# ITF_switching.net
KiCad netlist of a schematic drawn in EAGLE
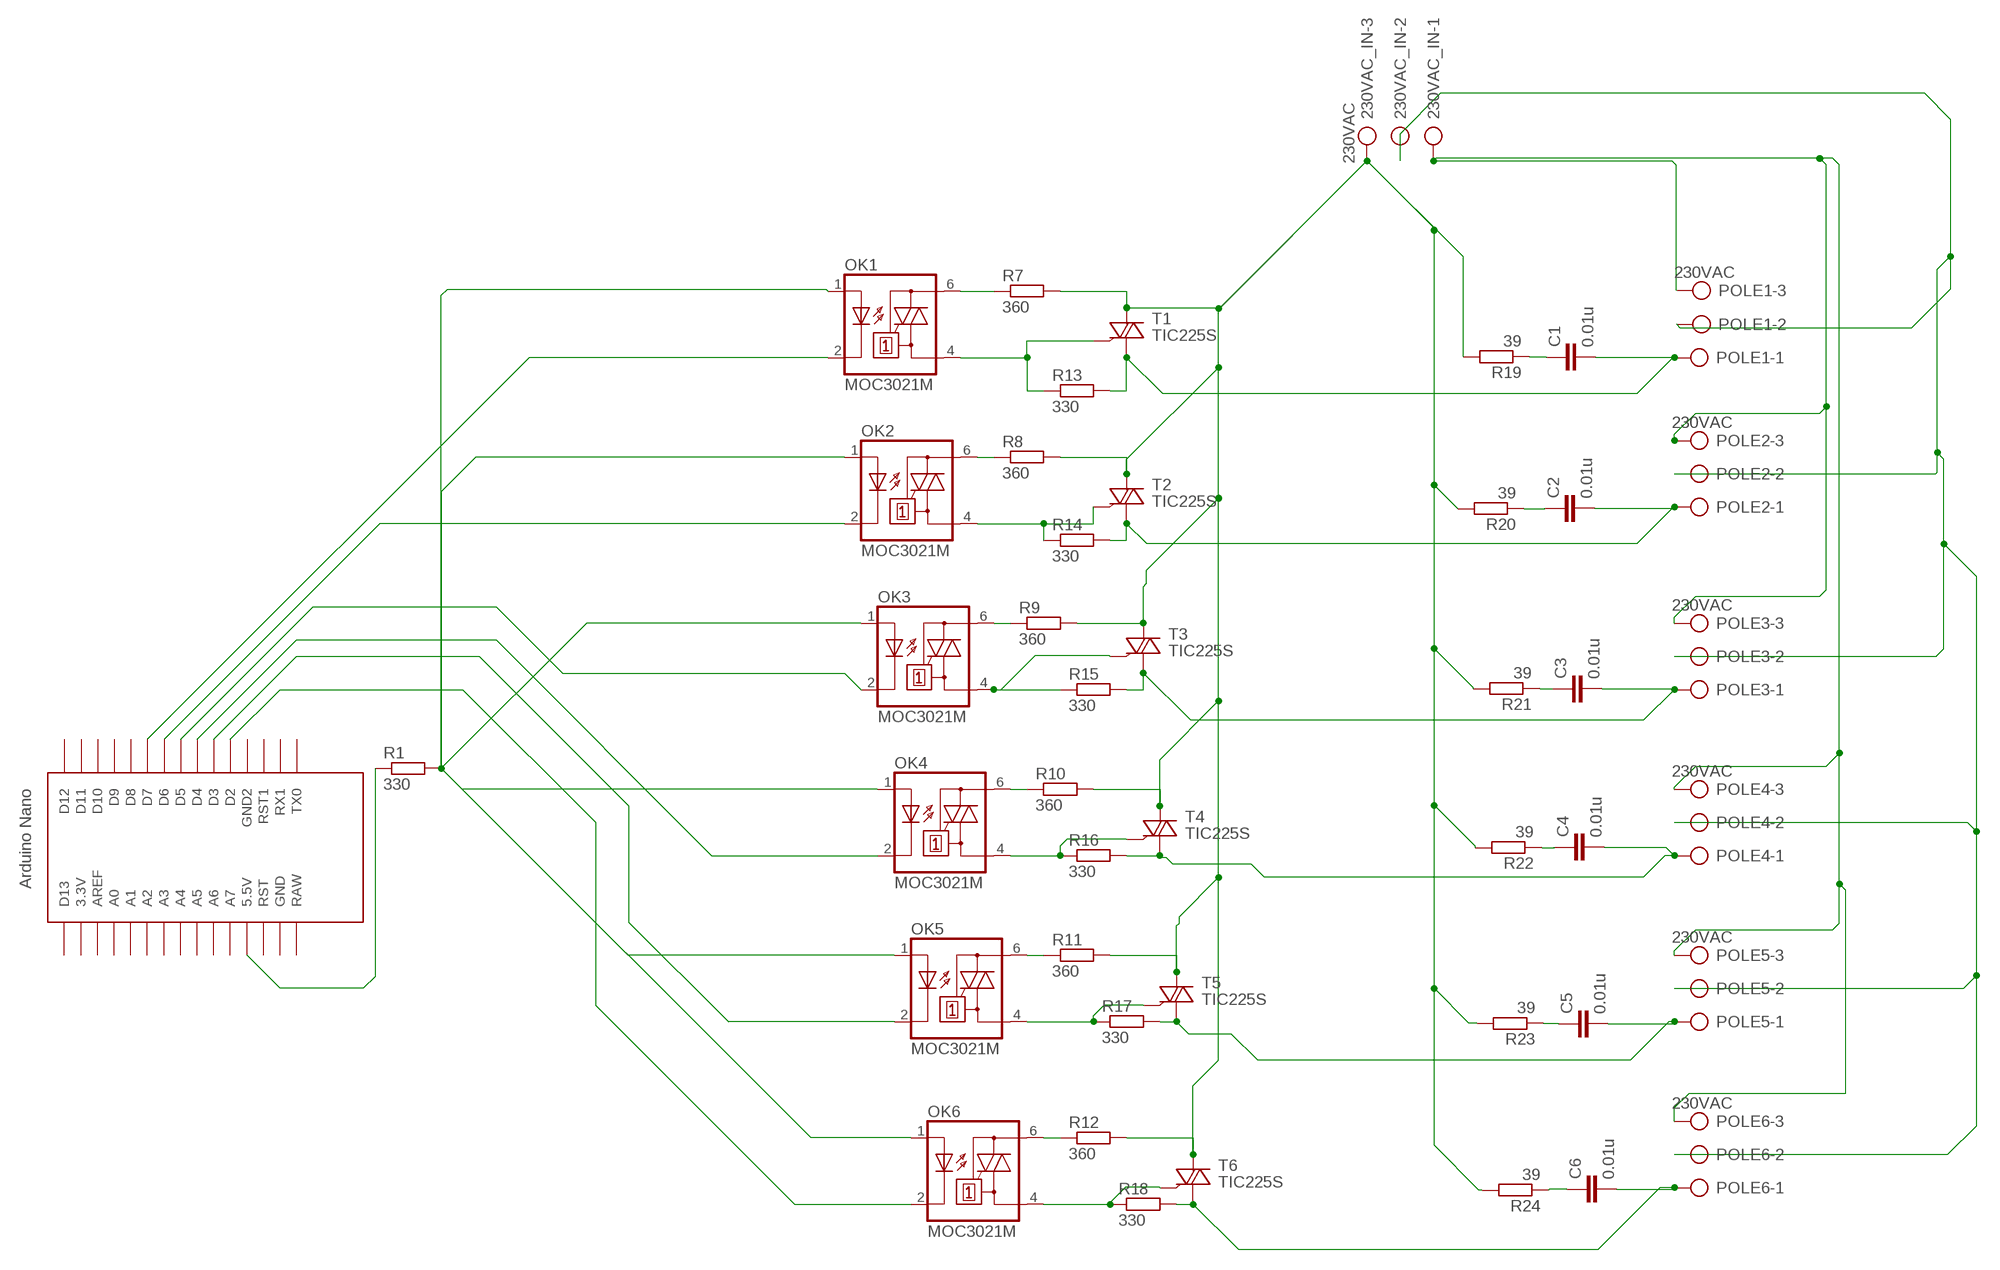
[diagram p0: schematic, sheet 1]

(export (version "E")
  (design (tool "Eeschema 10.0.6"))
  (components
    (comp (ref "230VAC_IN")
      (value "230VAC")
      (footprint "eagle-import:AK300_3")
      (libsource (lib "eagle-import") (part "AK300/3"))
    )
    (comp (ref "C1")
      (value "0.01u")
      (footprint "eagle-import:C2.5-6")
      (libsource (lib "eagle-import") (part "C2.5/6"))
    )
    (comp (ref "C2")
      (value "0.01u")
      (footprint "eagle-import:C2.5-6")
      (libsource (lib "eagle-import") (part "C2.5/6"))
    )
    (comp (ref "C3")
      (value "0.01u")
      (footprint "eagle-import:C2.5-6")
      (libsource (lib "eagle-import") (part "C2.5/6"))
    )
    (comp (ref "C4")
      (value "0.01u")
      (footprint "eagle-import:C2.5-6")
      (libsource (lib "eagle-import") (part "C2.5/6"))
    )
    (comp (ref "C5")
      (value "0.01u")
      (footprint "eagle-import:C2.5-6")
      (libsource (lib "eagle-import") (part "C2.5/6"))
    )
    (comp (ref "C6")
      (value "0.01u")
      (footprint "eagle-import:C2.5-6")
      (libsource (lib "eagle-import") (part "C2.5/6"))
    )
    (comp (ref "OK1")
      (value "MOC3021M")
      (footprint "eagle-import:DIL06")
      (fields (field (name "MF") "FAIRCHILD SEMICONDUCTOR") (field (name "MPN") "MOC3021-M"))
      (libsource (lib "eagle-import") (part "MOC30M21"))
    )
    (comp (ref "OK2")
      (value "MOC3021M")
      (footprint "eagle-import:DIL06")
      (fields (field (name "MF") "FAIRCHILD SEMICONDUCTOR") (field (name "MPN") "MOC3021-M"))
      (libsource (lib "eagle-import") (part "MOC30M21"))
    )
    (comp (ref "OK3")
      (value "MOC3021M")
      (footprint "eagle-import:DIL06")
      (fields (field (name "MF") "FAIRCHILD SEMICONDUCTOR") (field (name "MPN") "MOC3021-M"))
      (libsource (lib "eagle-import") (part "MOC30M21"))
    )
    (comp (ref "OK4")
      (value "MOC3021M")
      (footprint "eagle-import:DIL06")
      (fields (field (name "MF") "FAIRCHILD SEMICONDUCTOR") (field (name "MPN") "MOC3021-M"))
      (libsource (lib "eagle-import") (part "MOC30M21"))
    )
    (comp (ref "OK5")
      (value "MOC3021M")
      (footprint "eagle-import:DIL06")
      (fields (field (name "MF") "FAIRCHILD SEMICONDUCTOR") (field (name "MPN") "MOC3021-M"))
      (libsource (lib "eagle-import") (part "MOC30M21"))
    )
    (comp (ref "OK6")
      (value "MOC3021M")
      (footprint "eagle-import:DIL06")
      (fields (field (name "MF") "FAIRCHILD SEMICONDUCTOR") (field (name "MPN") "MOC3021-M"))
      (libsource (lib "eagle-import") (part "MOC30M21"))
    )
    (comp (ref "POLE1")
      (value "230VAC")
      (footprint "eagle-import:AK300_3")
      (libsource (lib "eagle-import") (part "AK300/3"))
    )
    (comp (ref "POLE2")
      (value "230VAC")
      (footprint "eagle-import:AK300_3")
      (libsource (lib "eagle-import") (part "AK300/3"))
    )
    (comp (ref "POLE3")
      (value "230VAC")
      (footprint "eagle-import:AK300_3")
      (libsource (lib "eagle-import") (part "AK300/3"))
    )
    (comp (ref "POLE4")
      (value "230VAC")
      (footprint "eagle-import:AK300_3")
      (libsource (lib "eagle-import") (part "AK300/3"))
    )
    (comp (ref "POLE5")
      (value "230VAC")
      (footprint "eagle-import:AK300_3")
      (libsource (lib "eagle-import") (part "AK300/3"))
    )
    (comp (ref "POLE6")
      (value "230VAC")
      (footprint "eagle-import:AK300_3")
      (libsource (lib "eagle-import") (part "AK300/3"))
    )
    (comp (ref "R1")
      (value "330")
      (footprint "eagle-import:0207_10")
      (libsource (lib "eagle-import") (part "R-EU_0207/10"))
    )
    (comp (ref "R7")
      (value "360")
      (footprint "eagle-import:0207_10")
      (libsource (lib "eagle-import") (part "R-EU_0207/10"))
    )
    (comp (ref "R8")
      (value "360")
      (footprint "eagle-import:0207_10")
      (libsource (lib "eagle-import") (part "R-EU_0207/10"))
    )
    (comp (ref "R9")
      (value "360")
      (footprint "eagle-import:0207_10")
      (libsource (lib "eagle-import") (part "R-EU_0207/10"))
    )
    (comp (ref "R10")
      (value "360")
      (footprint "eagle-import:0207_10")
      (libsource (lib "eagle-import") (part "R-EU_0207/10"))
    )
    (comp (ref "R11")
      (value "360")
      (footprint "eagle-import:0207_10")
      (libsource (lib "eagle-import") (part "R-EU_0207/10"))
    )
    (comp (ref "R12")
      (value "360")
      (footprint "eagle-import:0207_10")
      (libsource (lib "eagle-import") (part "R-EU_0207/10"))
    )
    (comp (ref "R13")
      (value "330")
      (footprint "eagle-import:0207_10")
      (libsource (lib "eagle-import") (part "R-EU_0207/10"))
    )
    (comp (ref "R14")
      (value "330")
      (footprint "eagle-import:0207_10")
      (libsource (lib "eagle-import") (part "R-EU_0207/10"))
    )
    (comp (ref "R15")
      (value "330")
      (footprint "eagle-import:0207_10")
      (libsource (lib "eagle-import") (part "R-EU_0207/10"))
    )
    (comp (ref "R16")
      (value "330")
      (footprint "eagle-import:0207_10")
      (libsource (lib "eagle-import") (part "R-EU_0207/10"))
    )
    (comp (ref "R17")
      (value "330")
      (footprint "eagle-import:0207_10")
      (libsource (lib "eagle-import") (part "R-EU_0207/10"))
    )
    (comp (ref "R18")
      (value "330")
      (footprint "eagle-import:0207_10")
      (libsource (lib "eagle-import") (part "R-EU_0207/10"))
    )
    (comp (ref "R19")
      (value "39")
      (footprint "eagle-import:0207_10")
      (libsource (lib "eagle-import") (part "R-EU_0207/10"))
    )
    (comp (ref "R20")
      (value "39")
      (footprint "eagle-import:0207_10")
      (libsource (lib "eagle-import") (part "R-EU_0207/10"))
    )
    (comp (ref "R21")
      (value "39")
      (footprint "eagle-import:0207_10")
      (libsource (lib "eagle-import") (part "R-EU_0207/10"))
    )
    (comp (ref "R22")
      (value "39")
      (footprint "eagle-import:0207_10")
      (libsource (lib "eagle-import") (part "R-EU_0207/10"))
    )
    (comp (ref "R23")
      (value "39")
      (footprint "eagle-import:0207_10")
      (libsource (lib "eagle-import") (part "R-EU_0207/10"))
    )
    (comp (ref "R24")
      (value "39")
      (footprint "eagle-import:0207_10")
      (libsource (lib "eagle-import") (part "R-EU_0207/10"))
    )
    (comp (ref "T1")
      (value "TIC225S")
      (footprint "eagle-import:TO220DS")
      (libsource (lib "eagle-import") (part "TIC225S"))
    )
    (comp (ref "T2")
      (value "TIC225S")
      (footprint "eagle-import:TO220DS")
      (libsource (lib "eagle-import") (part "TIC225S"))
    )
    (comp (ref "T3")
      (value "TIC225S")
      (footprint "eagle-import:TO220DS")
      (libsource (lib "eagle-import") (part "TIC225S"))
    )
    (comp (ref "T4")
      (value "TIC225S")
      (footprint "eagle-import:TO220DS")
      (libsource (lib "eagle-import") (part "TIC225S"))
    )
    (comp (ref "T5")
      (value "TIC225S")
      (footprint "eagle-import:TO220DS")
      (libsource (lib "eagle-import") (part "TIC225S"))
    )
    (comp (ref "T6")
      (value "TIC225S")
      (footprint "eagle-import:TO220DS")
      (libsource (lib "eagle-import") (part "TIC225S"))
    )
    (comp (ref "U$1")
      (value "NANO")
      (footprint "eagle-import:NANO")
      (libsource (lib "eagle-import") (part "NANO"))
    )
  )
  (nets
    (net (code "1") (name "Net-(230VAC_INA-KL)") (class "Default")
      (node (ref "230VAC_IN") (pin "1") (pinfunction "KL_1") (pintype "passive"))
      (node (ref "POLE1") (pin "3") (pinfunction "KL_3") (pintype "passive"))
      (node (ref "POLE2") (pin "3") (pinfunction "KL_3") (pintype "passive"))
      (node (ref "POLE3") (pin "3") (pinfunction "KL_3") (pintype "passive"))
      (node (ref "POLE4") (pin "3") (pinfunction "KL_3") (pintype "passive"))
      (node (ref "POLE5") (pin "3") (pinfunction "KL_3") (pintype "passive"))
      (node (ref "POLE6") (pin "3") (pinfunction "KL_3") (pintype "passive"))
    )
    (net (code "2") (name "Net-(230VAC_INB-KL)") (class "Default")
      (node (ref "230VAC_IN") (pin "2") (pinfunction "KL_2") (pintype "passive"))
      (node (ref "POLE1") (pin "2") (pinfunction "KL_2") (pintype "passive"))
      (node (ref "POLE2") (pin "2") (pinfunction "KL_2") (pintype "passive"))
      (node (ref "POLE3") (pin "2") (pinfunction "KL_2") (pintype "passive"))
      (node (ref "POLE4") (pin "2") (pinfunction "KL_2") (pintype "passive"))
      (node (ref "POLE5") (pin "2") (pinfunction "KL_2") (pintype "passive"))
      (node (ref "POLE6") (pin "2") (pinfunction "KL_2") (pintype "passive"))
    )
    (net (code "3") (name "Net-(230VAC_INC-KL)") (class "Default")
      (node (ref "230VAC_IN") (pin "3") (pinfunction "KL_3") (pintype "passive"))
      (node (ref "R10") (pin "2") (pinfunction "2_2") (pintype "passive"))
      (node (ref "R11") (pin "2") (pinfunction "2_2") (pintype "passive"))
      (node (ref "R12") (pin "2") (pinfunction "2_2") (pintype "passive"))
      (node (ref "R19") (pin "2") (pinfunction "2_2") (pintype "passive"))
      (node (ref "R20") (pin "2") (pinfunction "2_2") (pintype "passive"))
      (node (ref "R21") (pin "2") (pinfunction "2_2") (pintype "passive"))
      (node (ref "R22") (pin "2") (pinfunction "2_2") (pintype "passive"))
      (node (ref "R23") (pin "2") (pinfunction "2_2") (pintype "passive"))
      (node (ref "R24") (pin "2") (pinfunction "2_2") (pintype "passive"))
      (node (ref "R7") (pin "2") (pinfunction "2_2") (pintype "passive"))
      (node (ref "R8") (pin "2") (pinfunction "2_2") (pintype "passive"))
      (node (ref "R9") (pin "2") (pinfunction "2_2") (pintype "passive"))
      (node (ref "T1") (pin "A2") (pinfunction "A2_A2") (pintype "passive"))
      (node (ref "T2") (pin "A2") (pinfunction "A2_A2") (pintype "passive"))
      (node (ref "T3") (pin "A2") (pinfunction "A2_A2") (pintype "passive"))
      (node (ref "T4") (pin "A2") (pinfunction "A2_A2") (pintype "passive"))
      (node (ref "T5") (pin "A2") (pinfunction "A2_A2") (pintype "passive"))
      (node (ref "T6") (pin "A2") (pinfunction "A2_A2") (pintype "passive"))
    )
    (net (code "4") (name "Net-(C1-Pad1)") (class "Default")
      (node (ref "C1") (pin "1") (pinfunction "1_1") (pintype "passive"))
      (node (ref "R19") (pin "1") (pinfunction "1_1") (pintype "passive"))
    )
    (net (code "5") (name "Net-(C2-Pad1)") (class "Default")
      (node (ref "C2") (pin "1") (pinfunction "1_1") (pintype "passive"))
      (node (ref "R20") (pin "1") (pinfunction "1_1") (pintype "passive"))
    )
    (net (code "6") (name "Net-(C3-Pad1)") (class "Default")
      (node (ref "C3") (pin "1") (pinfunction "1_1") (pintype "passive"))
      (node (ref "R21") (pin "1") (pinfunction "1_1") (pintype "passive"))
    )
    (net (code "7") (name "Net-(C4-Pad1)") (class "Default")
      (node (ref "C4") (pin "1") (pinfunction "1_1") (pintype "passive"))
      (node (ref "R22") (pin "1") (pinfunction "1_1") (pintype "passive"))
    )
    (net (code "8") (name "Net-(C5-Pad1)") (class "Default")
      (node (ref "C5") (pin "1") (pinfunction "1_1") (pintype "passive"))
      (node (ref "R23") (pin "1") (pinfunction "1_1") (pintype "passive"))
    )
    (net (code "9") (name "Net-(C6-Pad1)") (class "Default")
      (node (ref "C6") (pin "1") (pinfunction "1_1") (pintype "passive"))
      (node (ref "R24") (pin "1") (pinfunction "1_1") (pintype "passive"))
    )
    (net (code "10") (name "Net-(OK1-A)") (class "Default")
      (node (ref "OK1") (pin "1") (pinfunction "A_1") (pintype "passive"))
      (node (ref "OK2") (pin "1") (pinfunction "A_1") (pintype "passive"))
      (node (ref "OK3") (pin "1") (pinfunction "A_1") (pintype "passive"))
      (node (ref "OK4") (pin "1") (pinfunction "A_1") (pintype "passive"))
      (node (ref "OK5") (pin "1") (pinfunction "A_1") (pintype "passive"))
      (node (ref "OK6") (pin "1") (pinfunction "A_1") (pintype "passive"))
      (node (ref "R1") (pin "2") (pinfunction "2_2") (pintype "passive"))
    )
    (net (code "11") (name "Net-(OK1-A1)") (class "Default")
      (node (ref "OK1") (pin "4") (pinfunction "A1_4") (pintype "passive"))
      (node (ref "R13") (pin "1") (pinfunction "1_1") (pintype "passive"))
      (node (ref "T1") (pin "G") (pinfunction "G_G") (pintype "passive"))
    )
    (net (code "12") (name "Net-(OK1-A2)") (class "Default")
      (node (ref "OK1") (pin "6") (pinfunction "A2_6") (pintype "passive"))
      (node (ref "R7") (pin "1") (pinfunction "1_1") (pintype "passive"))
    )
    (net (code "13") (name "Net-(OK1-C)") (class "Default")
      (node (ref "OK1") (pin "2") (pinfunction "C_2") (pintype "passive"))
      (node (ref "U$1") (pin "D7") (pinfunction "D7_D7") (pintype "bidirectional"))
    )
    (net (code "14") (name "Net-(OK2-A1)") (class "Default")
      (node (ref "OK2") (pin "4") (pinfunction "A1_4") (pintype "passive"))
      (node (ref "R14") (pin "1") (pinfunction "1_1") (pintype "passive"))
      (node (ref "T2") (pin "G") (pinfunction "G_G") (pintype "passive"))
    )
    (net (code "15") (name "Net-(OK2-A2)") (class "Default")
      (node (ref "OK2") (pin "6") (pinfunction "A2_6") (pintype "passive"))
      (node (ref "R8") (pin "1") (pinfunction "1_1") (pintype "passive"))
    )
    (net (code "16") (name "Net-(OK2-C)") (class "Default")
      (node (ref "OK2") (pin "2") (pinfunction "C_2") (pintype "passive"))
      (node (ref "U$1") (pin "D6") (pinfunction "D6_D6") (pintype "bidirectional"))
    )
    (net (code "17") (name "Net-(OK3-A1)") (class "Default")
      (node (ref "OK3") (pin "4") (pinfunction "A1_4") (pintype "passive"))
      (node (ref "R15") (pin "1") (pinfunction "1_1") (pintype "passive"))
      (node (ref "T3") (pin "G") (pinfunction "G_G") (pintype "passive"))
    )
    (net (code "18") (name "Net-(OK3-A2)") (class "Default")
      (node (ref "OK3") (pin "6") (pinfunction "A2_6") (pintype "passive"))
      (node (ref "R9") (pin "1") (pinfunction "1_1") (pintype "passive"))
    )
    (net (code "19") (name "Net-(OK3-C)") (class "Default")
      (node (ref "OK3") (pin "2") (pinfunction "C_2") (pintype "passive"))
      (node (ref "U$1") (pin "D5") (pinfunction "D5_D5") (pintype "bidirectional"))
    )
    (net (code "20") (name "Net-(OK4-A1)") (class "Default")
      (node (ref "OK4") (pin "4") (pinfunction "A1_4") (pintype "passive"))
      (node (ref "R16") (pin "1") (pinfunction "1_1") (pintype "passive"))
      (node (ref "T4") (pin "G") (pinfunction "G_G") (pintype "passive"))
    )
    (net (code "21") (name "Net-(OK4-A2)") (class "Default")
      (node (ref "OK4") (pin "6") (pinfunction "A2_6") (pintype "passive"))
      (node (ref "R10") (pin "1") (pinfunction "1_1") (pintype "passive"))
    )
    (net (code "22") (name "Net-(OK4-C)") (class "Default")
      (node (ref "OK4") (pin "2") (pinfunction "C_2") (pintype "passive"))
      (node (ref "U$1") (pin "D4") (pinfunction "D4_D4") (pintype "bidirectional"))
    )
    (net (code "23") (name "Net-(OK5-A1)") (class "Default")
      (node (ref "OK5") (pin "4") (pinfunction "A1_4") (pintype "passive"))
      (node (ref "R17") (pin "1") (pinfunction "1_1") (pintype "passive"))
      (node (ref "T5") (pin "G") (pinfunction "G_G") (pintype "passive"))
    )
    (net (code "24") (name "Net-(OK5-A2)") (class "Default")
      (node (ref "OK5") (pin "6") (pinfunction "A2_6") (pintype "passive"))
      (node (ref "R11") (pin "1") (pinfunction "1_1") (pintype "passive"))
    )
    (net (code "25") (name "Net-(OK5-C)") (class "Default")
      (node (ref "OK5") (pin "2") (pinfunction "C_2") (pintype "passive"))
      (node (ref "U$1") (pin "D3") (pinfunction "D3_D3") (pintype "bidirectional"))
    )
    (net (code "26") (name "Net-(OK6-A1)") (class "Default")
      (node (ref "OK6") (pin "4") (pinfunction "A1_4") (pintype "passive"))
      (node (ref "R18") (pin "1") (pinfunction "1_1") (pintype "passive"))
      (node (ref "T6") (pin "G") (pinfunction "G_G") (pintype "passive"))
    )
    (net (code "27") (name "Net-(OK6-A2)") (class "Default")
      (node (ref "OK6") (pin "6") (pinfunction "A2_6") (pintype "passive"))
      (node (ref "R12") (pin "1") (pinfunction "1_1") (pintype "passive"))
    )
    (net (code "28") (name "Net-(OK6-C)") (class "Default")
      (node (ref "OK6") (pin "2") (pinfunction "C_2") (pintype "passive"))
      (node (ref "U$1") (pin "D2") (pinfunction "D2_D2") (pintype "bidirectional"))
    )
    (net (code "29") (name "Net-(POLE1A-KL)") (class "Default")
      (node (ref "C1") (pin "2") (pinfunction "2_2") (pintype "passive"))
      (node (ref "POLE1") (pin "1") (pinfunction "KL_1") (pintype "passive"))
      (node (ref "R13") (pin "2") (pinfunction "2_2") (pintype "passive"))
      (node (ref "T1") (pin "A1") (pinfunction "A1_A1") (pintype "passive"))
    )
    (net (code "30") (name "Net-(POLE2A-KL)") (class "Default")
      (node (ref "C2") (pin "2") (pinfunction "2_2") (pintype "passive"))
      (node (ref "POLE2") (pin "1") (pinfunction "KL_1") (pintype "passive"))
      (node (ref "R14") (pin "2") (pinfunction "2_2") (pintype "passive"))
      (node (ref "T2") (pin "A1") (pinfunction "A1_A1") (pintype "passive"))
    )
    (net (code "31") (name "Net-(POLE3A-KL)") (class "Default")
      (node (ref "C3") (pin "2") (pinfunction "2_2") (pintype "passive"))
      (node (ref "POLE3") (pin "1") (pinfunction "KL_1") (pintype "passive"))
      (node (ref "R15") (pin "2") (pinfunction "2_2") (pintype "passive"))
      (node (ref "T3") (pin "A1") (pinfunction "A1_A1") (pintype "passive"))
    )
    (net (code "32") (name "Net-(POLE4A-KL)") (class "Default")
      (node (ref "C4") (pin "2") (pinfunction "2_2") (pintype "passive"))
      (node (ref "POLE4") (pin "1") (pinfunction "KL_1") (pintype "passive"))
      (node (ref "R16") (pin "2") (pinfunction "2_2") (pintype "passive"))
      (node (ref "T4") (pin "A1") (pinfunction "A1_A1") (pintype "passive"))
    )
    (net (code "33") (name "Net-(POLE5A-KL)") (class "Default")
      (node (ref "C5") (pin "2") (pinfunction "2_2") (pintype "passive"))
      (node (ref "POLE5") (pin "1") (pinfunction "KL_1") (pintype "passive"))
      (node (ref "R17") (pin "2") (pinfunction "2_2") (pintype "passive"))
      (node (ref "T5") (pin "A1") (pinfunction "A1_A1") (pintype "passive"))
    )
    (net (code "34") (name "Net-(POLE6A-KL)") (class "Default")
      (node (ref "C6") (pin "2") (pinfunction "2_2") (pintype "passive"))
      (node (ref "POLE6") (pin "1") (pinfunction "KL_1") (pintype "passive"))
      (node (ref "R18") (pin "2") (pinfunction "2_2") (pintype "passive"))
      (node (ref "T6") (pin "A1") (pinfunction "A1_A1") (pintype "passive"))
    )
    (net (code "35") (name "Net-(U$1-5.5V)") (class "Default")
      (node (ref "R1") (pin "1") (pinfunction "1_1") (pintype "passive"))
      (node (ref "U$1") (pin "5V") (pinfunction "5.5V_5V") (pintype "bidirectional"))
    )
    (net (code "36") (name "unconnected-(U$1-GND2-PadGND1)") (class "Default")
      (node (ref "U$1") (pin "GND1") (pinfunction "GND2_GND1") (pintype "bidirectional"))
    )
    (net (code "37") (name "unconnected-(U$1-Pad3.3V)") (class "Default")
      (node (ref "U$1") (pin "3.3V") (pinfunction "3.3V_3.3V") (pintype "bidirectional"))
    )
    (net (code "38") (name "unconnected-(U$1-PadA0)") (class "Default")
      (node (ref "U$1") (pin "A0") (pinfunction "A0_A0") (pintype "bidirectional"))
    )
    (net (code "39") (name "unconnected-(U$1-PadA1)") (class "Default")
      (node (ref "U$1") (pin "A1") (pinfunction "A1_A1") (pintype "bidirectional"))
    )
    (net (code "40") (name "unconnected-(U$1-PadA2)") (class "Default")
      (node (ref "U$1") (pin "A2") (pinfunction "A2_A2") (pintype "bidirectional"))
    )
    (net (code "41") (name "unconnected-(U$1-PadA3)") (class "Default")
      (node (ref "U$1") (pin "A3") (pinfunction "A3_A3") (pintype "bidirectional"))
    )
    (net (code "42") (name "unconnected-(U$1-PadA4)") (class "Default")
      (node (ref "U$1") (pin "A4") (pinfunction "A4_A4") (pintype "bidirectional"))
    )
    (net (code "43") (name "unconnected-(U$1-PadA5)") (class "Default")
      (node (ref "U$1") (pin "A5") (pinfunction "A5_A5") (pintype "bidirectional"))
    )
    (net (code "44") (name "unconnected-(U$1-PadA6)") (class "Default")
      (node (ref "U$1") (pin "A6") (pinfunction "A6_A6") (pintype "bidirectional"))
    )
    (net (code "45") (name "unconnected-(U$1-PadA7)") (class "Default")
      (node (ref "U$1") (pin "A7") (pinfunction "A7_A7") (pintype "bidirectional"))
    )
    (net (code "46") (name "unconnected-(U$1-PadAREF)") (class "Default")
      (node (ref "U$1") (pin "AREF") (pinfunction "AREF_AREF") (pintype "bidirectional"))
    )
    (net (code "47") (name "unconnected-(U$1-PadD8)") (class "Default")
      (node (ref "U$1") (pin "D8") (pinfunction "D8_D8") (pintype "bidirectional"))
    )
    (net (code "48") (name "unconnected-(U$1-PadD9)") (class "Default")
      (node (ref "U$1") (pin "D9") (pinfunction "D9_D9") (pintype "bidirectional"))
    )
    (net (code "49") (name "unconnected-(U$1-PadD10)") (class "Default")
      (node (ref "U$1") (pin "D10") (pinfunction "D10_D10") (pintype "bidirectional"))
    )
    (net (code "50") (name "unconnected-(U$1-PadD11)") (class "Default")
      (node (ref "U$1") (pin "D11") (pinfunction "D11_D11") (pintype "bidirectional"))
    )
    (net (code "51") (name "unconnected-(U$1-PadD12)") (class "Default")
      (node (ref "U$1") (pin "D12") (pinfunction "D12_D12") (pintype "bidirectional"))
    )
    (net (code "52") (name "unconnected-(U$1-PadD13)") (class "Default")
      (node (ref "U$1") (pin "D13") (pinfunction "D13_D13") (pintype "bidirectional"))
    )
    (net (code "53") (name "unconnected-(U$1-PadGND)") (class "Default")
      (node (ref "U$1") (pin "GND") (pinfunction "GND_GND") (pintype "bidirectional"))
    )
    (net (code "54") (name "unconnected-(U$1-PadICSP1)") (class "Default")
      (node (ref "U$1") (pin "ICSP1") (pinfunction "ICSP1_ICSP1") (pintype "bidirectional"))
    )
    (net (code "55") (name "unconnected-(U$1-PadICSP2)") (class "Default")
      (node (ref "U$1") (pin "ICSP2") (pinfunction "ICSP2_ICSP2") (pintype "bidirectional"))
    )
    (net (code "56") (name "unconnected-(U$1-PadICSP3)") (class "Default")
      (node (ref "U$1") (pin "ICSP3") (pinfunction "ICSP3_ICSP3") (pintype "bidirectional"))
    )
    (net (code "57") (name "unconnected-(U$1-PadICSP4)") (class "Default")
      (node (ref "U$1") (pin "ICSP4") (pinfunction "ICSP4_ICSP4") (pintype "bidirectional"))
    )
    (net (code "58") (name "unconnected-(U$1-PadICSP5)") (class "Default")
      (node (ref "U$1") (pin "ICSP5") (pinfunction "ICSP5_ICSP5") (pintype "bidirectional"))
    )
    (net (code "59") (name "unconnected-(U$1-PadICSP6)") (class "Default")
      (node (ref "U$1") (pin "ICSP6") (pinfunction "ICSP6_ICSP6") (pintype "bidirectional"))
    )
    (net (code "60") (name "unconnected-(U$1-PadRAW)") (class "Default")
      (node (ref "U$1") (pin "RAW") (pinfunction "RAW_RAW") (pintype "bidirectional"))
    )
    (net (code "61") (name "unconnected-(U$1-PadRST)") (class "Default")
      (node (ref "U$1") (pin "RST") (pinfunction "RST_RST") (pintype "bidirectional"))
    )
    (net (code "62") (name "unconnected-(U$1-PadRST1)") (class "Default")
      (node (ref "U$1") (pin "RST1") (pinfunction "RST1_RST1") (pintype "bidirectional"))
    )
    (net (code "63") (name "unconnected-(U$1-PadRX1)") (class "Default")
      (node (ref "U$1") (pin "RX1") (pinfunction "RX1_RX1") (pintype "bidirectional"))
    )
    (net (code "64") (name "unconnected-(U$1-PadTX0)") (class "Default")
      (node (ref "U$1") (pin "TX0") (pinfunction "TX0_TX0") (pintype "bidirectional"))
    )
  )
)
